# UTAP2022_DAUGHTER_v1_1.net
KiCad netlist of a schematic drawn in EAGLE
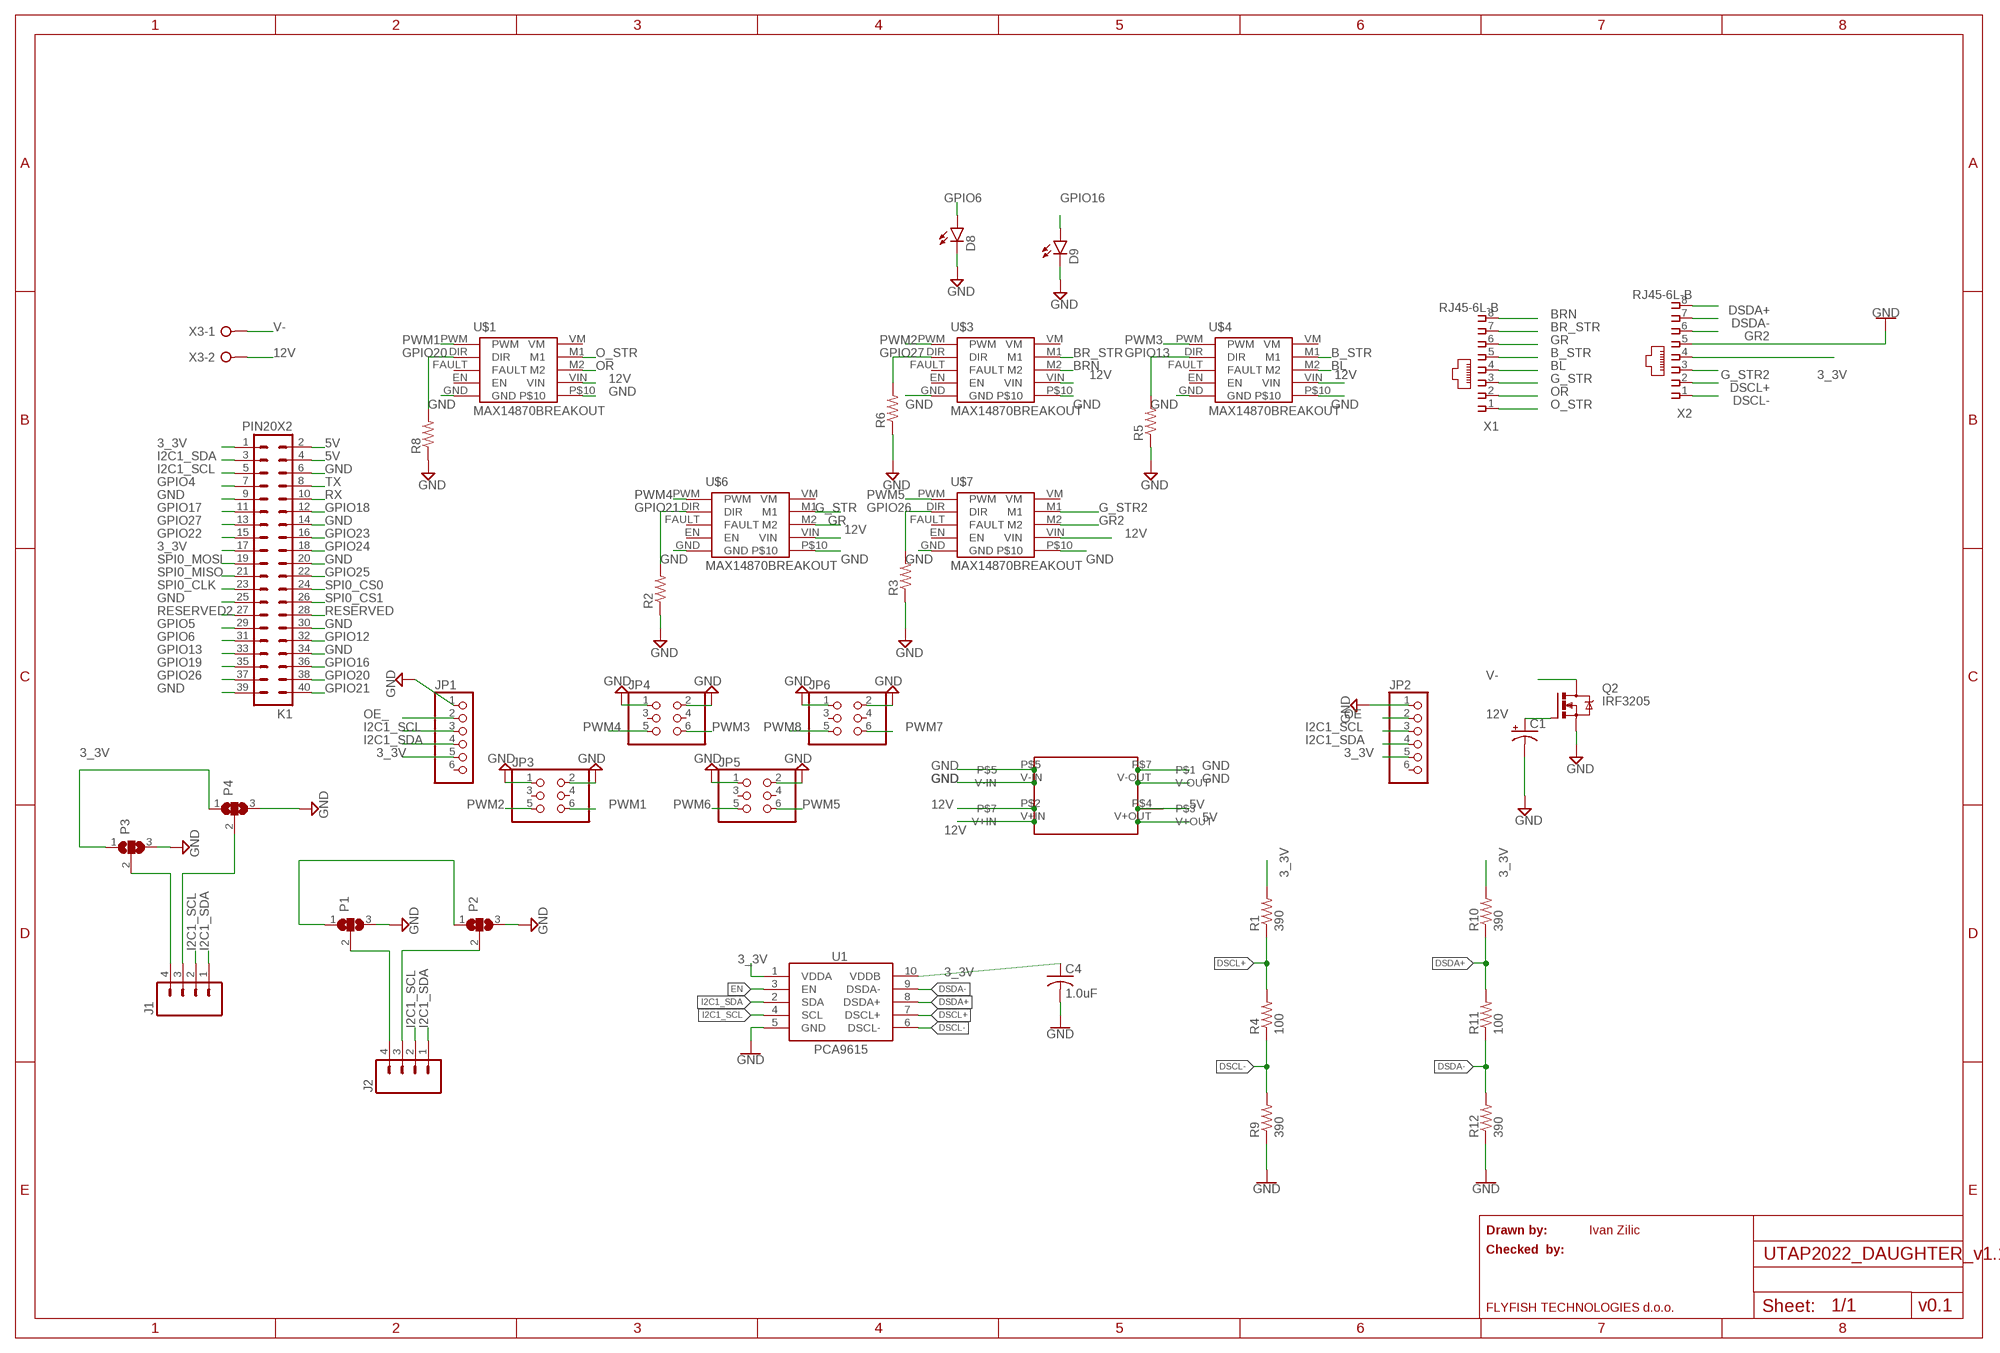
[diagram p0: schematic, sheet 1]

(export (version "E")
  (design (tool "Eeschema 10.0.6"))
  (components
    (comp (ref "C1")
      (value "CAP_POLPTH1")
      (footprint "eagle-import:CPOL-RADIAL-100UF-25V")
      (libsource (lib "eagle-import") (part "CAP_POLPTH1"))
    )
    (comp (ref "C4")
      (value "1.0uF")
      (footprint "eagle-import:C050-024X044")
      (libsource (lib "eagle-import") (part "C-US050-024X044"))
    )
    (comp (ref "D8")
      (value "LED5MM")
      (footprint "eagle-import:LED5MM")
      (libsource (lib "eagle-import") (part "LED5MM"))
    )
    (comp (ref "D9")
      (value "LED5MM")
      (footprint "eagle-import:LED5MM")
      (libsource (lib "eagle-import") (part "LED5MM"))
    )
    (comp (ref "J1")
      (value "M04PTH")
      (footprint "eagle-import:1X04")
      (libsource (lib "eagle-import") (part "M04PTH"))
    )
    (comp (ref "J2")
      (value "M04PTH")
      (footprint "eagle-import:1X04")
      (libsource (lib "eagle-import") (part "M04PTH"))
    )
    (comp (ref "JP1")
      (value "PINHD-1X6")
      (footprint "eagle-import:1X06")
      (libsource (lib "eagle-import") (part "PINHD-1X6"))
    )
    (comp (ref "JP2")
      (value "PINHD-1X6")
      (footprint "eagle-import:1X06")
      (libsource (lib "eagle-import") (part "PINHD-1X6"))
    )
    (comp (ref "JP3")
      (value "PINHD-2X3")
      (footprint "eagle-import:2X03")
      (libsource (lib "eagle-import") (part "PINHD-2X3"))
    )
    (comp (ref "JP4")
      (value "PINHD-2X3")
      (footprint "eagle-import:2X03")
      (libsource (lib "eagle-import") (part "PINHD-2X3"))
    )
    (comp (ref "JP5")
      (value "PINHD-2X3")
      (footprint "eagle-import:2X03")
      (libsource (lib "eagle-import") (part "PINHD-2X3"))
    )
    (comp (ref "JP6")
      (value "PINHD-2X3")
      (footprint "eagle-import:2X03")
      (libsource (lib "eagle-import") (part "PINHD-2X3"))
    )
    (comp (ref "K1")
      (value "PIN20X2")
      (footprint "eagle-import:PIN_20X2")
      (libsource (lib "eagle-import") (part "PIN20X2"))
    )
    (comp (ref "P1")
      (value "SJ2W")
      (footprint "eagle-import:SJ_2")
      (libsource (lib "eagle-import") (part "SJ2W"))
    )
    (comp (ref "P2")
      (value "SJ2W")
      (footprint "eagle-import:SJ_2")
      (libsource (lib "eagle-import") (part "SJ2W"))
    )
    (comp (ref "P3")
      (value "SJ2W")
      (footprint "eagle-import:SJ_2")
      (libsource (lib "eagle-import") (part "SJ2W"))
    )
    (comp (ref "P4")
      (value "SJ2W")
      (footprint "eagle-import:SJ_2")
      (libsource (lib "eagle-import") (part "SJ2W"))
    )
    (comp (ref "Q2")
      (value "IRF3205")
      (footprint "eagle-import:TO220BV")
      (libsource (lib "eagle-import") (part "IRF540"))
    )
    (comp (ref "R1")
      (value "390")
      (footprint "eagle-import:0204_7")
      (libsource (lib "eagle-import") (part "R-US_0204/7"))
    )
    (comp (ref "R2")
      (value "R-US_0204/7")
      (footprint "eagle-import:0204_7")
      (libsource (lib "eagle-import") (part "R-US_0204/7"))
    )
    (comp (ref "R3")
      (value "R-US_0204/7")
      (footprint "eagle-import:0204_7")
      (libsource (lib "eagle-import") (part "R-US_0204/7"))
    )
    (comp (ref "R4")
      (value "100")
      (footprint "eagle-import:0204_7")
      (libsource (lib "eagle-import") (part "R-US_0204/7"))
    )
    (comp (ref "R5")
      (value "R-US_0204/7")
      (footprint "eagle-import:0204_7")
      (libsource (lib "eagle-import") (part "R-US_0204/7"))
    )
    (comp (ref "R6")
      (value "R-US_0204/7")
      (footprint "eagle-import:0204_7")
      (libsource (lib "eagle-import") (part "R-US_0204/7"))
    )
    (comp (ref "R8")
      (value "R-US_0204/7")
      (footprint "eagle-import:0204_7")
      (libsource (lib "eagle-import") (part "R-US_0204/7"))
    )
    (comp (ref "R9")
      (value "390")
      (footprint "eagle-import:0204_7")
      (libsource (lib "eagle-import") (part "R-US_0204/7"))
    )
    (comp (ref "R10")
      (value "390")
      (footprint "eagle-import:0204_7")
      (libsource (lib "eagle-import") (part "R-US_0204/7"))
    )
    (comp (ref "R11")
      (value "100")
      (footprint "eagle-import:0204_7")
      (libsource (lib "eagle-import") (part "R-US_0204/7"))
    )
    (comp (ref "R12")
      (value "390")
      (footprint "eagle-import:0204_7")
      (libsource (lib "eagle-import") (part "R-US_0204/7"))
    )
    (comp (ref "U$1")
      (value "MAX14870BREAKOUT")
      (footprint "eagle-import:MAX14870_BREAKOUT")
      (libsource (lib "eagle-import") (part "MAX14870BREAKOUT"))
    )
    (comp (ref "U$3")
      (value "MAX14870BREAKOUT")
      (footprint "eagle-import:MAX14870_BREAKOUT")
      (libsource (lib "eagle-import") (part "MAX14870BREAKOUT"))
    )
    (comp (ref "U$4")
      (value "MAX14870BREAKOUT")
      (footprint "eagle-import:MAX14870_BREAKOUT")
      (libsource (lib "eagle-import") (part "MAX14870BREAKOUT"))
    )
    (comp (ref "U$6")
      (value "MAX14870BREAKOUT")
      (footprint "eagle-import:MAX14870_BREAKOUT")
      (libsource (lib "eagle-import") (part "MAX14870BREAKOUT"))
    )
    (comp (ref "U$7")
      (value "MAX14870BREAKOUT")
      (footprint "eagle-import:MAX14870_BREAKOUT")
      (libsource (lib "eagle-import") (part "MAX14870BREAKOUT"))
    )
    (comp (ref "U$9")
      (value "MP1584EN")
      (footprint "eagle-import:BUCK_CONV")
      (libsource (lib "eagle-import") (part "MP1584EN"))
    )
    (comp (ref "U1")
      (value "PCA9615")
      (footprint "eagle-import:TSSOP10")
      (libsource (lib "eagle-import") (part "PCA9615"))
    )
    (comp (ref "X1")
      (value "RJ45-6L-B")
      (footprint "eagle-import:RJ45-NO-SHIELD")
      (libsource (lib "eagle-import") (part "RJ45-6L-B"))
    )
    (comp (ref "X2")
      (value "RJ45-6L-B")
      (footprint "eagle-import:RJ45-NO-SHIELD")
      (libsource (lib "eagle-import") (part "RJ45-6L-B"))
    )
    (comp (ref "X3")
      (value "W237-02P")
      (footprint "eagle-import:W237-132")
      (libsource (lib "eagle-import") (part "W237-02P"))
    )
  )
  (nets
    (net (code "1") (name "/3_3V") (class "Default")
      (node (ref "C4") (pin "1") (pinfunction "1_1") (pintype "passive"))
      (node (ref "JP1") (pin "5") (pinfunction "5_5") (pintype "passive"))
      (node (ref "JP2") (pin "5") (pinfunction "5_5") (pintype "passive"))
      (node (ref "K1") (pin "1") (pinfunction "1_1") (pintype "passive"))
      (node (ref "K1") (pin "17") (pinfunction "17_17") (pintype "passive"))
      (node (ref "P1") (pin "1") (pinfunction "1_1") (pintype "passive"))
      (node (ref "P2") (pin "1") (pinfunction "1_1") (pintype "passive"))
      (node (ref "P3") (pin "1") (pinfunction "1_1") (pintype "passive"))
      (node (ref "P4") (pin "1") (pinfunction "1_1") (pintype "passive"))
      (node (ref "R1") (pin "2") (pinfunction "2_2") (pintype "passive"))
      (node (ref "R10") (pin "2") (pinfunction "2_2") (pintype "passive"))
      (node (ref "U1") (pin "1") (pinfunction "VDDA_1") (pintype "bidirectional"))
      (node (ref "U1") (pin "10") (pinfunction "VDDB_10") (pintype "bidirectional"))
      (node (ref "X2") (pin "4") (pinfunction "4_4") (pintype "passive"))
    )
    (net (code "2") (name "/5V") (class "Default")
      (node (ref "K1") (pin "2") (pinfunction "2_2") (pintype "passive"))
      (node (ref "K1") (pin "4") (pinfunction "4_4") (pintype "passive"))
      (node (ref "U$9") (pin "P$4") (pinfunction "P$3_P$4") (pintype "bidirectional"))
      (node (ref "U$9") (pin "V+OUT") (pinfunction "V+OUT_V+OUT") (pintype "bidirectional"))
    )
    (net (code "3") (name "/12V") (class "Default")
      (node (ref "C1") (pin "1") (pinfunction "+_1") (pintype "passive"))
      (node (ref "Q2") (pin "G") (pinfunction "G_G") (pintype "passive"))
      (node (ref "U$1") (pin "VIN") (pinfunction "VIN_VIN") (pintype "bidirectional"))
      (node (ref "U$3") (pin "VIN") (pinfunction "VIN_VIN") (pintype "bidirectional"))
      (node (ref "U$4") (pin "VIN") (pinfunction "VIN_VIN") (pintype "bidirectional"))
      (node (ref "U$6") (pin "VIN") (pinfunction "VIN_VIN") (pintype "bidirectional"))
      (node (ref "U$7") (pin "VIN") (pinfunction "VIN_VIN") (pintype "bidirectional"))
      (node (ref "U$9") (pin "P$2") (pinfunction "P$7_P$2") (pintype "bidirectional"))
      (node (ref "U$9") (pin "V+IN") (pinfunction "V+IN_V+IN") (pintype "bidirectional"))
      (node (ref "X3") (pin "2") (pinfunction "KL_2") (pintype "passive"))
    )
    (net (code "4") (name "/BL") (class "Default")
      (node (ref "U$4") (pin "M2") (pinfunction "M2_M2") (pintype "bidirectional"))
      (node (ref "X1") (pin "4") (pinfunction "4_4") (pintype "passive"))
    )
    (net (code "5") (name "/BRN") (class "Default")
      (node (ref "U$3") (pin "M2") (pinfunction "M2_M2") (pintype "bidirectional"))
      (node (ref "X1") (pin "8") (pinfunction "8_8") (pintype "passive"))
    )
    (net (code "6") (name "/BR_STR") (class "Default")
      (node (ref "U$3") (pin "M1") (pinfunction "M1_M1") (pintype "bidirectional"))
      (node (ref "X1") (pin "7") (pinfunction "7_7") (pintype "passive"))
    )
    (net (code "7") (name "/B_STR") (class "Default")
      (node (ref "U$4") (pin "M1") (pinfunction "M1_M1") (pintype "bidirectional"))
      (node (ref "X1") (pin "5") (pinfunction "5_5") (pintype "passive"))
    )
    (net (code "8") (name "/GPIO4") (class "Default")
      (node (ref "K1") (pin "7") (pinfunction "7_7") (pintype "passive"))
    )
    (net (code "9") (name "/GPIO5") (class "Default")
      (node (ref "K1") (pin "29") (pinfunction "29_29") (pintype "passive"))
    )
    (net (code "10") (name "/GPIO6") (class "Default")
      (node (ref "D8") (pin "A") (pinfunction "A_A") (pintype "passive"))
      (node (ref "K1") (pin "31") (pinfunction "31_31") (pintype "passive"))
    )
    (net (code "11") (name "/GPIO12") (class "Default")
      (node (ref "K1") (pin "32") (pinfunction "32_32") (pintype "passive"))
    )
    (net (code "12") (name "/GPIO13") (class "Default")
      (node (ref "K1") (pin "33") (pinfunction "33_33") (pintype "passive"))
      (node (ref "R5") (pin "2") (pinfunction "2_2") (pintype "passive"))
      (node (ref "U$4") (pin "DIR") (pinfunction "DIR_DIR") (pintype "bidirectional"))
    )
    (net (code "13") (name "/GPIO16") (class "Default")
      (node (ref "D9") (pin "A") (pinfunction "A_A") (pintype "passive"))
      (node (ref "K1") (pin "36") (pinfunction "36_36") (pintype "passive"))
    )
    (net (code "14") (name "/GPIO17") (class "Default")
      (node (ref "K1") (pin "11") (pinfunction "11_11") (pintype "passive"))
    )
    (net (code "15") (name "/GPIO18") (class "Default")
      (node (ref "K1") (pin "12") (pinfunction "12_12") (pintype "passive"))
    )
    (net (code "16") (name "/GPIO19") (class "Default")
      (node (ref "K1") (pin "35") (pinfunction "35_35") (pintype "passive"))
    )
    (net (code "17") (name "/GPIO20") (class "Default")
      (node (ref "K1") (pin "38") (pinfunction "38_38") (pintype "passive"))
      (node (ref "R8") (pin "2") (pinfunction "2_2") (pintype "passive"))
      (node (ref "U$1") (pin "DIR") (pinfunction "DIR_DIR") (pintype "bidirectional"))
    )
    (net (code "18") (name "/GPIO21") (class "Default")
      (node (ref "K1") (pin "40") (pinfunction "40_40") (pintype "passive"))
      (node (ref "R2") (pin "2") (pinfunction "2_2") (pintype "passive"))
      (node (ref "U$6") (pin "DIR") (pinfunction "DIR_DIR") (pintype "bidirectional"))
    )
    (net (code "19") (name "/GPIO22") (class "Default")
      (node (ref "K1") (pin "15") (pinfunction "15_15") (pintype "passive"))
    )
    (net (code "20") (name "/GPIO23") (class "Default")
      (node (ref "K1") (pin "16") (pinfunction "16_16") (pintype "passive"))
    )
    (net (code "21") (name "/GPIO24") (class "Default")
      (node (ref "K1") (pin "18") (pinfunction "18_18") (pintype "passive"))
    )
    (net (code "22") (name "/GPIO25") (class "Default")
      (node (ref "K1") (pin "22") (pinfunction "22_22") (pintype "passive"))
    )
    (net (code "23") (name "/GPIO26") (class "Default")
      (node (ref "K1") (pin "37") (pinfunction "37_37") (pintype "passive"))
      (node (ref "R3") (pin "2") (pinfunction "2_2") (pintype "passive"))
      (node (ref "U$7") (pin "DIR") (pinfunction "DIR_DIR") (pintype "bidirectional"))
    )
    (net (code "24") (name "/GPIO27") (class "Default")
      (node (ref "K1") (pin "13") (pinfunction "13_13") (pintype "passive"))
      (node (ref "R6") (pin "2") (pinfunction "2_2") (pintype "passive"))
      (node (ref "U$3") (pin "DIR") (pinfunction "DIR_DIR") (pintype "bidirectional"))
    )
    (net (code "25") (name "/GR") (class "Default")
      (node (ref "U$6") (pin "M2") (pinfunction "M2_M2") (pintype "bidirectional"))
      (node (ref "X1") (pin "6") (pinfunction "6_6") (pintype "passive"))
    )
    (net (code "26") (name "/GR2") (class "Default")
      (node (ref "U$7") (pin "M2") (pinfunction "M2_M2") (pintype "bidirectional"))
      (node (ref "X2") (pin "6") (pinfunction "6_6") (pintype "passive"))
    )
    (net (code "27") (name "/G_STR") (class "Default")
      (node (ref "U$6") (pin "M1") (pinfunction "M1_M1") (pintype "bidirectional"))
      (node (ref "X1") (pin "3") (pinfunction "3_3") (pintype "passive"))
    )
    (net (code "28") (name "/G_STR2") (class "Default")
      (node (ref "U$7") (pin "M1") (pinfunction "M1_M1") (pintype "bidirectional"))
      (node (ref "X2") (pin "3") (pinfunction "3_3") (pintype "passive"))
    )
    (net (code "29") (name "/OE") (class "Default")
      (node (ref "JP2") (pin "2") (pinfunction "2_2") (pintype "passive"))
    )
    (net (code "30") (name "/OE_") (class "Default")
      (node (ref "JP1") (pin "2") (pinfunction "2_2") (pintype "passive"))
    )
    (net (code "31") (name "/OR") (class "Default")
      (node (ref "U$1") (pin "M2") (pinfunction "M2_M2") (pintype "bidirectional"))
      (node (ref "X1") (pin "2") (pinfunction "2_2") (pintype "passive"))
    )
    (net (code "32") (name "/O_STR") (class "Default")
      (node (ref "U$1") (pin "M1") (pinfunction "M1_M1") (pintype "bidirectional"))
      (node (ref "X1") (pin "1") (pinfunction "1_1") (pintype "passive"))
    )
    (net (code "33") (name "/PWM1") (class "Default")
      (node (ref "JP3") (pin "6") (pinfunction "6_6") (pintype "passive"))
      (node (ref "U$1") (pin "PWM") (pinfunction "PWM_PWM") (pintype "bidirectional"))
    )
    (net (code "34") (name "/PWM2") (class "Default")
      (node (ref "JP3") (pin "5") (pinfunction "5_5") (pintype "passive"))
      (node (ref "U$3") (pin "PWM") (pinfunction "PWM_PWM") (pintype "bidirectional"))
    )
    (net (code "35") (name "/PWM3") (class "Default")
      (node (ref "JP4") (pin "6") (pinfunction "6_6") (pintype "passive"))
      (node (ref "U$4") (pin "PWM") (pinfunction "PWM_PWM") (pintype "bidirectional"))
    )
    (net (code "36") (name "/PWM4") (class "Default")
      (node (ref "JP4") (pin "5") (pinfunction "5_5") (pintype "passive"))
      (node (ref "U$6") (pin "PWM") (pinfunction "PWM_PWM") (pintype "bidirectional"))
    )
    (net (code "37") (name "/PWM5") (class "Default")
      (node (ref "JP5") (pin "6") (pinfunction "6_6") (pintype "passive"))
      (node (ref "U$7") (pin "PWM") (pinfunction "PWM_PWM") (pintype "bidirectional"))
    )
    (net (code "38") (name "/PWM6") (class "Default")
      (node (ref "JP5") (pin "5") (pinfunction "5_5") (pintype "passive"))
    )
    (net (code "39") (name "/PWM7") (class "Default")
      (node (ref "JP6") (pin "6") (pinfunction "6_6") (pintype "passive"))
    )
    (net (code "40") (name "/PWM8") (class "Default")
      (node (ref "JP6") (pin "5") (pinfunction "5_5") (pintype "passive"))
    )
    (net (code "41") (name "/RESERVED") (class "Default")
      (node (ref "K1") (pin "28") (pinfunction "28_28") (pintype "passive"))
    )
    (net (code "42") (name "/RESERVED2") (class "Default")
      (node (ref "K1") (pin "27") (pinfunction "27_27") (pintype "passive"))
    )
    (net (code "43") (name "/RX") (class "Default")
      (node (ref "K1") (pin "10") (pinfunction "10_10") (pintype "passive"))
    )
    (net (code "44") (name "/SPI0_CLK") (class "Default")
      (node (ref "K1") (pin "23") (pinfunction "23_23") (pintype "passive"))
    )
    (net (code "45") (name "/SPI0_CS0") (class "Default")
      (node (ref "K1") (pin "24") (pinfunction "24_24") (pintype "passive"))
    )
    (net (code "46") (name "/SPI0_CS1") (class "Default")
      (node (ref "K1") (pin "26") (pinfunction "26_26") (pintype "passive"))
    )
    (net (code "47") (name "/SPI0_MISO") (class "Default")
      (node (ref "K1") (pin "21") (pinfunction "21_21") (pintype "passive"))
    )
    (net (code "48") (name "/SPI0_MOSI") (class "Default")
      (node (ref "K1") (pin "19") (pinfunction "19_19") (pintype "passive"))
    )
    (net (code "49") (name "/TX") (class "Default")
      (node (ref "K1") (pin "8") (pinfunction "8_8") (pintype "passive"))
    )
    (net (code "50") (name "/V-") (class "Default")
      (node (ref "Q2") (pin "D") (pinfunction "D_D") (pintype "passive"))
      (node (ref "X3") (pin "1") (pinfunction "KL_1") (pintype "passive"))
    )
    (net (code "51") (name "DSCL+") (class "Default")
      (node (ref "R1") (pin "1") (pinfunction "1_1") (pintype "passive"))
      (node (ref "R4") (pin "2") (pinfunction "2_2") (pintype "passive"))
      (node (ref "U1") (pin "7") (pinfunction "DSCL+_7") (pintype "bidirectional"))
      (node (ref "X2") (pin "2") (pinfunction "2_2") (pintype "passive"))
    )
    (net (code "52") (name "DSCL-") (class "Default")
      (node (ref "R4") (pin "1") (pinfunction "1_1") (pintype "passive"))
      (node (ref "R9") (pin "2") (pinfunction "2_2") (pintype "passive"))
      (node (ref "U1") (pin "6") (pinfunction "DSCL-_6") (pintype "bidirectional"))
      (node (ref "X2") (pin "1") (pinfunction "1_1") (pintype "passive"))
    )
    (net (code "53") (name "DSDA+") (class "Default")
      (node (ref "R10") (pin "1") (pinfunction "1_1") (pintype "passive"))
      (node (ref "R11") (pin "2") (pinfunction "2_2") (pintype "passive"))
      (node (ref "U1") (pin "8") (pinfunction "DSDA+_8") (pintype "bidirectional"))
      (node (ref "X2") (pin "8") (pinfunction "8_8") (pintype "passive"))
    )
    (net (code "54") (name "DSDA-") (class "Default")
      (node (ref "R11") (pin "1") (pinfunction "1_1") (pintype "passive"))
      (node (ref "R12") (pin "2") (pinfunction "2_2") (pintype "passive"))
      (node (ref "U1") (pin "9") (pinfunction "DSDA-_9") (pintype "bidirectional"))
      (node (ref "X2") (pin "7") (pinfunction "7_7") (pintype "passive"))
    )
    (net (code "55") (name "EN") (class "Default")
      (node (ref "U1") (pin "3") (pinfunction "EN_3") (pintype "bidirectional"))
    )
    (net (code "56") (name "GND") (class "Default")
      (node (ref "C1") (pin "2") (pinfunction "-_2") (pintype "passive"))
      (node (ref "C4") (pin "2") (pinfunction "2_2") (pintype "passive"))
      (node (ref "D8") (pin "K") (pinfunction "C_K") (pintype "passive"))
      (node (ref "D9") (pin "K") (pinfunction "C_K") (pintype "passive"))
      (node (ref "JP1") (pin "1") (pinfunction "1_1") (pintype "passive"))
      (node (ref "JP2") (pin "1") (pinfunction "1_1") (pintype "passive"))
      (node (ref "JP3") (pin "1") (pinfunction "1_1") (pintype "passive"))
      (node (ref "JP3") (pin "2") (pinfunction "2_2") (pintype "passive"))
      (node (ref "JP4") (pin "1") (pinfunction "1_1") (pintype "passive"))
      (node (ref "JP4") (pin "2") (pinfunction "2_2") (pintype "passive"))
      (node (ref "JP5") (pin "1") (pinfunction "1_1") (pintype "passive"))
      (node (ref "JP5") (pin "2") (pinfunction "2_2") (pintype "passive"))
      (node (ref "JP6") (pin "1") (pinfunction "1_1") (pintype "passive"))
      (node (ref "JP6") (pin "2") (pinfunction "2_2") (pintype "passive"))
      (node (ref "K1") (pin "14") (pinfunction "14_14") (pintype "passive"))
      (node (ref "K1") (pin "20") (pinfunction "20_20") (pintype "passive"))
      (node (ref "K1") (pin "25") (pinfunction "25_25") (pintype "passive"))
      (node (ref "K1") (pin "30") (pinfunction "30_30") (pintype "passive"))
      (node (ref "K1") (pin "34") (pinfunction "34_34") (pintype "passive"))
      (node (ref "K1") (pin "39") (pinfunction "39_39") (pintype "passive"))
      (node (ref "K1") (pin "6") (pinfunction "6_6") (pintype "passive"))
      (node (ref "K1") (pin "9") (pinfunction "9_9") (pintype "passive"))
      (node (ref "P1") (pin "3") (pinfunction "3_3") (pintype "passive"))
      (node (ref "P2") (pin "3") (pinfunction "3_3") (pintype "passive"))
      (node (ref "P3") (pin "3") (pinfunction "3_3") (pintype "passive"))
      (node (ref "P4") (pin "3") (pinfunction "3_3") (pintype "passive"))
      (node (ref "Q2") (pin "S") (pinfunction "S_S") (pintype "passive"))
      (node (ref "R12") (pin "1") (pinfunction "1_1") (pintype "passive"))
      (node (ref "R2") (pin "1") (pinfunction "1_1") (pintype "passive"))
      (node (ref "R3") (pin "1") (pinfunction "1_1") (pintype "passive"))
      (node (ref "R5") (pin "1") (pinfunction "1_1") (pintype "passive"))
      (node (ref "R6") (pin "1") (pinfunction "1_1") (pintype "passive"))
      (node (ref "R8") (pin "1") (pinfunction "1_1") (pintype "passive"))
      (node (ref "R9") (pin "1") (pinfunction "1_1") (pintype "passive"))
      (node (ref "U$1") (pin "GND") (pinfunction "GND_GND") (pintype "bidirectional"))
      (node (ref "U$1") (pin "P$10") (pinfunction "P$10_P$10") (pintype "bidirectional"))
      (node (ref "U$3") (pin "GND") (pinfunction "GND_GND") (pintype "bidirectional"))
      (node (ref "U$3") (pin "P$10") (pinfunction "P$10_P$10") (pintype "bidirectional"))
      (node (ref "U$4") (pin "GND") (pinfunction "GND_GND") (pintype "bidirectional"))
      (node (ref "U$4") (pin "P$10") (pinfunction "P$10_P$10") (pintype "bidirectional"))
      (node (ref "U$6") (pin "GND") (pinfunction "GND_GND") (pintype "bidirectional"))
      (node (ref "U$6") (pin "P$10") (pinfunction "P$10_P$10") (pintype "bidirectional"))
      (node (ref "U$7") (pin "GND") (pinfunction "GND_GND") (pintype "bidirectional"))
      (node (ref "U$7") (pin "P$10") (pinfunction "P$10_P$10") (pintype "bidirectional"))
      (node (ref "U$9") (pin "P$5") (pinfunction "P$5_P$5") (pintype "bidirectional"))
      (node (ref "U$9") (pin "P$7") (pinfunction "P$1_P$7") (pintype "bidirectional"))
      (node (ref "U$9") (pin "V-IN") (pinfunction "V-IN_V-IN") (pintype "bidirectional"))
      (node (ref "U$9") (pin "V-OUT") (pinfunction "V-OUT_V-OUT") (pintype "bidirectional"))
      (node (ref "U1") (pin "5") (pinfunction "GND_5") (pintype "bidirectional"))
      (node (ref "X2") (pin "5") (pinfunction "5_5") (pintype "passive"))
    )
    (net (code "57") (name "I2C1_SCL") (class "Default")
      (node (ref "J1") (pin "2") (pinfunction "2_2") (pintype "passive"))
      (node (ref "J2") (pin "2") (pinfunction "2_2") (pintype "passive"))
      (node (ref "JP1") (pin "3") (pinfunction "3_3") (pintype "passive"))
      (node (ref "JP2") (pin "3") (pinfunction "3_3") (pintype "passive"))
      (node (ref "K1") (pin "5") (pinfunction "5_5") (pintype "passive"))
      (node (ref "U1") (pin "4") (pinfunction "SCL_4") (pintype "bidirectional"))
    )
    (net (code "58") (name "I2C1_SDA") (class "Default")
      (node (ref "J1") (pin "1") (pinfunction "1_1") (pintype "passive"))
      (node (ref "J2") (pin "1") (pinfunction "1_1") (pintype "passive"))
      (node (ref "JP1") (pin "4") (pinfunction "4_4") (pintype "passive"))
      (node (ref "JP2") (pin "4") (pinfunction "4_4") (pintype "passive"))
      (node (ref "K1") (pin "3") (pinfunction "3_3") (pintype "passive"))
      (node (ref "U1") (pin "2") (pinfunction "SDA_2") (pintype "bidirectional"))
    )
    (net (code "59") (name "Net-(J1-Pad3)") (class "Default")
      (node (ref "J1") (pin "3") (pinfunction "3_3") (pintype "passive"))
      (node (ref "P4") (pin "2") (pinfunction "2_2") (pintype "passive"))
    )
    (net (code "60") (name "Net-(J1-Pad4)") (class "Default")
      (node (ref "J1") (pin "4") (pinfunction "4_4") (pintype "passive"))
      (node (ref "P3") (pin "2") (pinfunction "2_2") (pintype "passive"))
    )
    (net (code "61") (name "Net-(J2-Pad3)") (class "Default")
      (node (ref "J2") (pin "3") (pinfunction "3_3") (pintype "passive"))
      (node (ref "P2") (pin "2") (pinfunction "2_2") (pintype "passive"))
    )
    (net (code "62") (name "Net-(J2-Pad4)") (class "Default")
      (node (ref "J2") (pin "4") (pinfunction "4_4") (pintype "passive"))
      (node (ref "P1") (pin "2") (pinfunction "2_2") (pintype "passive"))
    )
    (net (code "63") (name "unconnected-(JP1-Pad6)") (class "Default")
      (node (ref "JP1") (pin "6") (pinfunction "6_6") (pintype "passive"))
    )
    (net (code "64") (name "unconnected-(JP2-Pad6)") (class "Default")
      (node (ref "JP2") (pin "6") (pinfunction "6_6") (pintype "passive"))
    )
    (net (code "65") (name "unconnected-(JP3-Pad3)") (class "Default")
      (node (ref "JP3") (pin "3") (pinfunction "3_3") (pintype "passive"))
    )
    (net (code "66") (name "unconnected-(JP3-Pad4)") (class "Default")
      (node (ref "JP3") (pin "4") (pinfunction "4_4") (pintype "passive"))
    )
    (net (code "67") (name "unconnected-(JP4-Pad3)") (class "Default")
      (node (ref "JP4") (pin "3") (pinfunction "3_3") (pintype "passive"))
    )
    (net (code "68") (name "unconnected-(JP4-Pad4)") (class "Default")
      (node (ref "JP4") (pin "4") (pinfunction "4_4") (pintype "passive"))
    )
    (net (code "69") (name "unconnected-(JP5-Pad3)") (class "Default")
      (node (ref "JP5") (pin "3") (pinfunction "3_3") (pintype "passive"))
    )
    (net (code "70") (name "unconnected-(JP5-Pad4)") (class "Default")
      (node (ref "JP5") (pin "4") (pinfunction "4_4") (pintype "passive"))
    )
    (net (code "71") (name "unconnected-(JP6-Pad3)") (class "Default")
      (node (ref "JP6") (pin "3") (pinfunction "3_3") (pintype "passive"))
    )
    (net (code "72") (name "unconnected-(JP6-Pad4)") (class "Default")
      (node (ref "JP6") (pin "4") (pinfunction "4_4") (pintype "passive"))
    )
    (net (code "73") (name "unconnected-(U$1-PadEN)") (class "Default")
      (node (ref "U$1") (pin "EN") (pinfunction "EN_EN") (pintype "bidirectional"))
    )
    (net (code "74") (name "unconnected-(U$1-PadFAULT)") (class "Default")
      (node (ref "U$1") (pin "FAULT") (pinfunction "FAULT_FAULT") (pintype "bidirectional"))
    )
    (net (code "75") (name "unconnected-(U$1-PadVM)") (class "Default")
      (node (ref "U$1") (pin "VM") (pinfunction "VM_VM") (pintype "bidirectional"))
    )
    (net (code "76") (name "unconnected-(U$3-PadEN)") (class "Default")
      (node (ref "U$3") (pin "EN") (pinfunction "EN_EN") (pintype "bidirectional"))
    )
    (net (code "77") (name "unconnected-(U$3-PadFAULT)") (class "Default")
      (node (ref "U$3") (pin "FAULT") (pinfunction "FAULT_FAULT") (pintype "bidirectional"))
    )
    (net (code "78") (name "unconnected-(U$3-PadVM)") (class "Default")
      (node (ref "U$3") (pin "VM") (pinfunction "VM_VM") (pintype "bidirectional"))
    )
    (net (code "79") (name "unconnected-(U$4-PadEN)") (class "Default")
      (node (ref "U$4") (pin "EN") (pinfunction "EN_EN") (pintype "bidirectional"))
    )
    (net (code "80") (name "unconnected-(U$4-PadFAULT)") (class "Default")
      (node (ref "U$4") (pin "FAULT") (pinfunction "FAULT_FAULT") (pintype "bidirectional"))
    )
    (net (code "81") (name "unconnected-(U$4-PadVM)") (class "Default")
      (node (ref "U$4") (pin "VM") (pinfunction "VM_VM") (pintype "bidirectional"))
    )
    (net (code "82") (name "unconnected-(U$6-PadEN)") (class "Default")
      (node (ref "U$6") (pin "EN") (pinfunction "EN_EN") (pintype "bidirectional"))
    )
    (net (code "83") (name "unconnected-(U$6-PadFAULT)") (class "Default")
      (node (ref "U$6") (pin "FAULT") (pinfunction "FAULT_FAULT") (pintype "bidirectional"))
    )
    (net (code "84") (name "unconnected-(U$6-PadVM)") (class "Default")
      (node (ref "U$6") (pin "VM") (pinfunction "VM_VM") (pintype "bidirectional"))
    )
    (net (code "85") (name "unconnected-(U$7-PadEN)") (class "Default")
      (node (ref "U$7") (pin "EN") (pinfunction "EN_EN") (pintype "bidirectional"))
    )
    (net (code "86") (name "unconnected-(U$7-PadFAULT)") (class "Default")
      (node (ref "U$7") (pin "FAULT") (pinfunction "FAULT_FAULT") (pintype "bidirectional"))
    )
    (net (code "87") (name "unconnected-(U$7-PadVM)") (class "Default")
      (node (ref "U$7") (pin "VM") (pinfunction "VM_VM") (pintype "bidirectional"))
    )
  )
)
